# EPS_DCDC_RLCL-FPF.net
KiCad netlist of a schematic drawn in Altium Designer
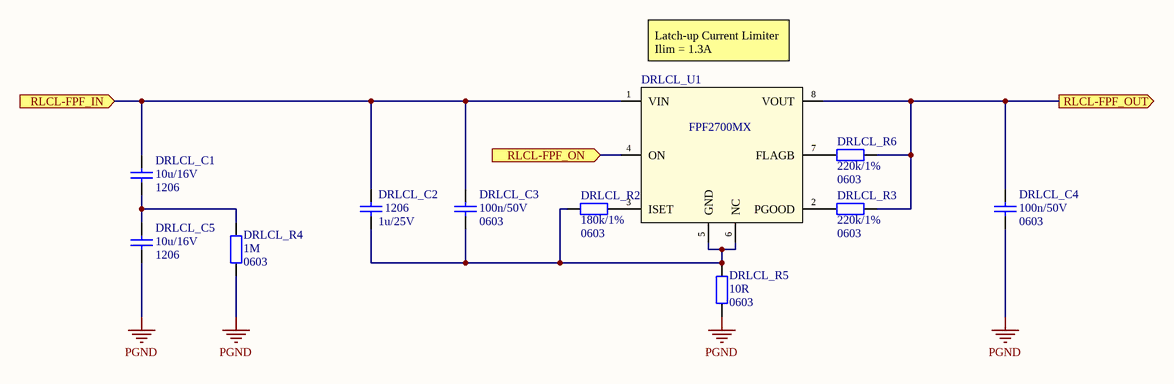
[diagram p0: EPS_DCDC_RLCL-FPF.SchDoc]

(export (version "E")
  (design (tool "Eeschema 10.0.6"))
  (components
    (comp (ref "DRLCL_C1")
      (value "10u/16V")
      (footprint "SMD_Capacitor_1206")
      (description "Ceramic Cap Kemet COTS 10u/16V X7R 1206")
      (fields
        (field (name "MANUFACTURERPARTNUMBER") "C1206T106K4RACTU")
        (field (name "MANUFACTURER") "Kemet")
        (field (name "PACKGE") "1206")
      )
      (libsource (lib "capacitors") (part "Cer_C1206T106K4RACTU"))
    )
    (comp (ref "DRLCL_C2")
      (value "1u/25V")
      (footprint "SMD_Capacitor_1206")
      (description "Ceramic Cap Kemet COTS 1u/25V X7R 1206")
      (fields
        (field (name "MANUFACTURERPARTNUMBER") "C1206T105K3RALTU")
        (field (name "MANUFACTURER") "Kemet")
        (field (name "PACKAGE") "1206")
      )
      (libsource (lib "capacitors") (part "Cer_C1206T105K3RALTU"))
    )
    (comp (ref "DRLCL_C3")
      (value "100n/50V")
      (footprint "SMD_Capacitor_0603")
      (description "Ceramic Cap Murata Automotive 100n/50V X7R 0603")
      (fields
        (field (name "MANUFACTURER") "Murata")
        (field (name "MANUFACTURERPARTNUMBER") "GCJ188R71H104KA12D")
        (field (name "PACKAGE") "0603")
      )
      (libsource (lib "capacitors") (part "Cer_GCJ188R71H104KA12D"))
    )
    (comp (ref "DRLCL_C4")
      (value "100n/50V")
      (footprint "SMD_Capacitor_0603")
      (description "Ceramic Cap Murata Automotive 100n/50V X7R 0603")
      (fields
        (field (name "MANUFACTURER") "Murata")
        (field (name "MANUFACTURERPARTNUMBER") "GCJ188R71H104KA12D")
        (field (name "PACKAGE") "0603")
      )
      (libsource (lib "capacitors") (part "Cer_GCJ188R71H104KA12D"))
    )
    (comp (ref "DRLCL_C5")
      (value "10u/16V")
      (footprint "SMD_Capacitor_1206")
      (description "Ceramic Cap Kemet COTS 10u/16V X7R 1206")
      (fields
        (field (name "MANUFACTURERPARTNUMBER") "C1206T106K4RACTU")
        (field (name "MANUFACTURER") "Kemet")
        (field (name "PACKGE") "1206")
      )
      (libsource (lib "capacitors") (part "Cer_C1206T106K4RACTU"))
    )
    (comp (ref "DRLCL_R2")
      (value "180k/1%")
      (footprint "SMD_Resistor_0603")
      (fields (field (name "PACKAGE") "0603"))
      (libsource (lib "") (part "Res_1"))
    )
    (comp (ref "DRLCL_R3")
      (value "220k/1%")
      (footprint "SMD_Resistor_0603")
      (fields (field (name "PACKAGE") "0603"))
      (libsource (lib "") (part "Res_1"))
    )
    (comp (ref "DRLCL_R4")
      (value "1M")
      (footprint "SMD_Resistor_0603")
      (fields (field (name "PACKAGE") "0603"))
      (libsource (lib "resistors") (part "Res"))
    )
    (comp (ref "DRLCL_R5")
      (value "10R")
      (footprint "SMD_Resistor_0603")
      (fields (field (name "PACKAGE") "0603"))
      (libsource (lib "") (part "Res_2"))
    )
    (comp (ref "DRLCL_R6")
      (value "220k/1%")
      (footprint "SMD_Resistor_0603")
      (fields (field (name "PACKAGE") "0603"))
      (libsource (lib "") (part "Res_1"))
    )
    (comp (ref "DRLCL_U1")
      (value "FPF2700MX")
      (footprint "SOIC-8-N")
      (description "Adj over-current protection 0.4-2A, Load Switch")
      (fields (field (name "MANUFACTURER") "Fairchild Semiconductor"))
      (libsource (lib "microcircuits") (part "FPF2700MX"))
    )
  )
  (nets
    (net (code "1") (name "/RLCL-FPF_IN") (class "Default")
      (node (ref "DRLCL_C1") (pin "1") (pinfunction "1_1") (pintype "passive"))
      (node (ref "DRLCL_C2") (pin "1") (pinfunction "1_1") (pintype "passive"))
      (node (ref "DRLCL_C3") (pin "1") (pinfunction "1_1") (pintype "passive"))
      (node (ref "DRLCL_U1") (pin "1") (pinfunction "VIN_1") (pintype "passive"))
    )
    (net (code "2") (name "/RLCL-FPF_ON") (class "Default")
      (node (ref "DRLCL_U1") (pin "4") (pinfunction "ON_4") (pintype "passive"))
    )
    (net (code "3") (name "/RLCL-FPF_OUT") (class "Default")
      (node (ref "DRLCL_C4") (pin "1") (pinfunction "1_1") (pintype "passive"))
      (node (ref "DRLCL_R3") (pin "2") (pinfunction "2_2") (pintype "passive"))
      (node (ref "DRLCL_R6") (pin "2") (pinfunction "2_2") (pintype "passive"))
      (node (ref "DRLCL_U1") (pin "8") (pinfunction "VOUT_8") (pintype "passive"))
    )
    (net (code "4") (name "Net-(DRLCL_C1-Pad2)") (class "Default")
      (node (ref "DRLCL_C1") (pin "2") (pinfunction "2_2") (pintype "passive"))
      (node (ref "DRLCL_C5") (pin "1") (pinfunction "1_1") (pintype "passive"))
      (node (ref "DRLCL_R4") (pin "2") (pinfunction "2_2") (pintype "passive"))
    )
    (net (code "5") (name "Net-(DRLCL_U1-FLAGB)") (class "Default")
      (node (ref "DRLCL_R6") (pin "1") (pinfunction "1_1") (pintype "passive"))
      (node (ref "DRLCL_U1") (pin "7") (pinfunction "FLAGB_7") (pintype "passive"))
    )
    (net (code "6") (name "Net-(DRLCL_U1-GND)") (class "Default")
      (node (ref "DRLCL_C2") (pin "2") (pinfunction "2_2") (pintype "passive"))
      (node (ref "DRLCL_C3") (pin "2") (pinfunction "2_2") (pintype "passive"))
      (node (ref "DRLCL_R2") (pin "1") (pinfunction "1_1") (pintype "passive"))
      (node (ref "DRLCL_R5") (pin "1") (pinfunction "1_1") (pintype "passive"))
      (node (ref "DRLCL_U1") (pin "5") (pinfunction "GND_5") (pintype "passive"))
      (node (ref "DRLCL_U1") (pin "6") (pinfunction "NC_6") (pintype "passive"))
    )
    (net (code "7") (name "Net-(DRLCL_U1-ISET)") (class "Default")
      (node (ref "DRLCL_R2") (pin "2") (pinfunction "2_2") (pintype "passive"))
      (node (ref "DRLCL_U1") (pin "3") (pinfunction "ISET_3") (pintype "passive"))
    )
    (net (code "8") (name "Net-(DRLCL_U1-PGOOD)") (class "Default")
      (node (ref "DRLCL_R3") (pin "1") (pinfunction "1_1") (pintype "passive"))
      (node (ref "DRLCL_U1") (pin "2") (pinfunction "PGOOD_2") (pintype "passive"))
    )
    (net (code "9") (name "PGND") (class "Default")
      (node (ref "DRLCL_C4") (pin "2") (pinfunction "2_2") (pintype "passive"))
      (node (ref "DRLCL_C5") (pin "2") (pinfunction "2_2") (pintype "passive"))
      (node (ref "DRLCL_R4") (pin "1") (pinfunction "1_1") (pintype "passive"))
      (node (ref "DRLCL_R5") (pin "2") (pinfunction "2_2") (pintype "passive"))
    )
  )
)
